# light_sensor_basic.net
KiCad netlist of a schematic drawn in EAGLE
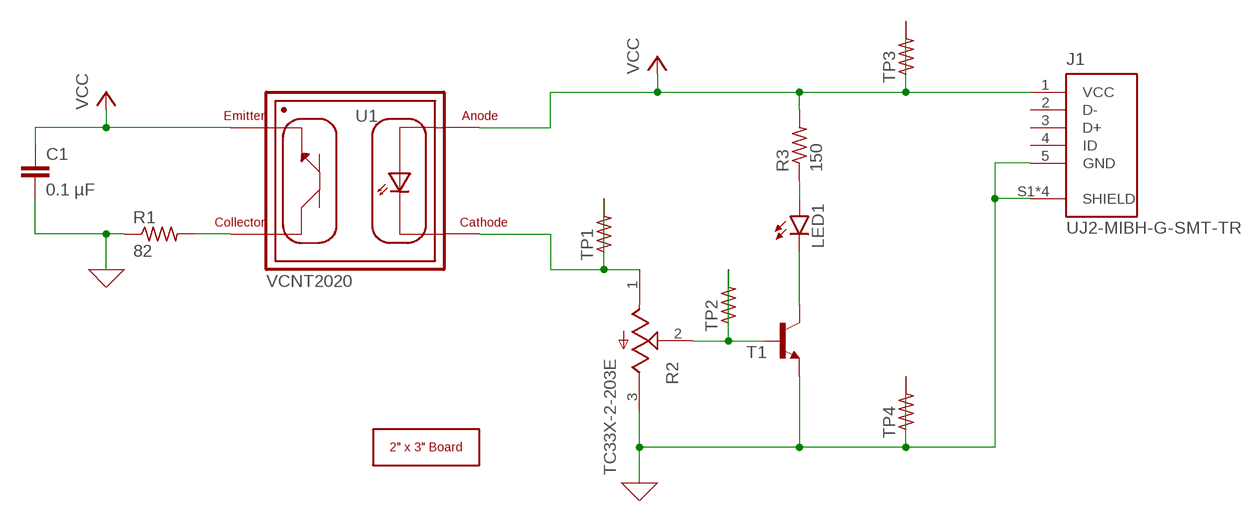
[diagram p0: schematic, sheet 1]

(export (version "E")
  (design (tool "Eeschema 10.0.6"))
  (components
    (comp (ref "C1")
      (value "0.1 µF")
      (footprint "eagle-import:C1206")
      (libsource (lib "eagle-import") (part "C-EUC1206"))
    )
    (comp (ref "J1")
      (value "UJ2-MIBH-G-SMT-TR")
      (footprint "eagle-import:CUI_UJ2-MIBH-G-SMT-TR")
      (fields (field (name "MANUFACTURER") "CUI"))
      (libsource (lib "eagle-import") (part "UJ2-MIBH-G-SMT-TR"))
    )
    (comp (ref "LED1")
      (value "LEDCHIPLED_0805")
      (footprint "eagle-import:CHIPLED_0805")
      (libsource (lib "eagle-import") (part "LEDCHIPLED_0805"))
    )
    (comp (ref "R1")
      (value "82")
      (footprint "eagle-import:R0805")
      (libsource (lib "eagle-import") (part "R-US_R0805"))
    )
    (comp (ref "R2")
      (value "TC33X-2-203E")
      (footprint "eagle-import:TRIM_TC33X-2-203E")
      (fields (field (name "DIGIKEY_PART_NUMBER") "TC33X-2-203ETR-ND") (field (name "MF") "Bourns"))
      (libsource (lib "eagle-import") (part "TC33X-2-203E"))
    )
    (comp (ref "R3")
      (value "150")
      (footprint "eagle-import:R0805")
      (libsource (lib "eagle-import") (part "R-US_R0805"))
    )
    (comp (ref "T1")
      (value "BFS17-NPN-SOT23-BEC")
      (footprint "eagle-import:SOT23-BEC")
      (libsource (lib "eagle-import") (part "-NPN-SOT23-BECBFS17"))
    )
    (comp (ref "TP1")
      (value "R-US_R1206")
      (footprint "eagle-import:R1206")
      (libsource (lib "eagle-import") (part "R-US_R1206"))
    )
    (comp (ref "TP2")
      (value "R-US_R1206")
      (footprint "eagle-import:R1206")
      (libsource (lib "eagle-import") (part "R-US_R1206"))
    )
    (comp (ref "TP3")
      (value "R-US_R1206")
      (footprint "eagle-import:R1206")
      (libsource (lib "eagle-import") (part "R-US_R1206"))
    )
    (comp (ref "TP4")
      (value "R-US_R1206")
      (footprint "eagle-import:R1206")
      (libsource (lib "eagle-import") (part "R-US_R1206"))
    )
    (comp (ref "U$1")
      (value "2X3_BOARD_V2")
      (footprint "eagle-import:2X3_BOARD_V2")
      (libsource (lib "eagle-import") (part "2X3_BOARD_V2"))
    )
    (comp (ref "U1")
      (value "VCNT2020")
      (footprint "eagle-import:XDCR_VCNT2020")
      (fields (field (name "DIGIKEY_PART_NUMBER") "VCNT2020TR-ND") (field (name "MF") "Vishay"))
      (libsource (lib "eagle-import") (part "VCNT2020"))
    )
  )
  (nets
    (net (code "1") (name "GND") (class "Default")
      (node (ref "C1") (pin "2") (pinfunction "2_2") (pintype "passive"))
      (node (ref "J1") (pin "5") (pinfunction "GND_5") (pintype "power_in"))
      (node (ref "J1") (pin "S1") (pinfunction "SHIELD_S1") (pintype "passive"))
      (node (ref "J1") (pin "S2") (pinfunction "SHIELD_S2") (pintype "passive"))
      (node (ref "J1") (pin "S3") (pinfunction "SHIELD_S3") (pintype "passive"))
      (node (ref "J1") (pin "S4") (pinfunction "SHIELD_S4") (pintype "passive"))
      (node (ref "R1") (pin "1") (pinfunction "1_1") (pintype "passive"))
      (node (ref "R2") (pin "3") (pinfunction "CW_3") (pintype "passive"))
      (node (ref "T1") (pin "E") (pinfunction "E_E") (pintype "passive"))
      (node (ref "TP4") (pin "1") (pinfunction "1_1") (pintype "passive"))
      (node (ref "TP4") (pin "2") (pinfunction "2_2") (pintype "passive"))
    )
    (net (code "2") (name "Net-(LED1-PadA)") (class "Default")
      (node (ref "LED1") (pin "A") (pinfunction "A_A") (pintype "passive"))
      (node (ref "R3") (pin "1") (pinfunction "1_1") (pintype "passive"))
    )
    (net (code "3") (name "Net-(LED1-PadC)") (class "Default")
      (node (ref "LED1") (pin "C") (pinfunction "C_C") (pintype "passive"))
      (node (ref "T1") (pin "C") (pinfunction "C_C") (pintype "passive"))
    )
    (net (code "4") (name "Net-(R2-CCW)") (class "Default")
      (node (ref "R2") (pin "1") (pinfunction "CCW_1") (pintype "passive"))
      (node (ref "TP1") (pin "1") (pinfunction "1_1") (pintype "passive"))
      (node (ref "TP1") (pin "2") (pinfunction "2_2") (pintype "passive"))
      (node (ref "U1") (pin "4") (pinfunction "CATHODE_4") (pintype "passive"))
    )
    (net (code "5") (name "Net-(R2-W)") (class "Default")
      (node (ref "R2") (pin "2") (pinfunction "W_2") (pintype "passive"))
      (node (ref "T1") (pin "B") (pinfunction "B_B") (pintype "passive"))
      (node (ref "TP2") (pin "1") (pinfunction "1_1") (pintype "passive"))
      (node (ref "TP2") (pin "2") (pinfunction "2_2") (pintype "passive"))
    )
    (net (code "6") (name "Net-(U1-COLLECTOR)") (class "Default")
      (node (ref "R1") (pin "2") (pinfunction "2_2") (pintype "passive"))
      (node (ref "U1") (pin "2") (pinfunction "COLLECTOR_2") (pintype "passive"))
    )
    (net (code "7") (name "VCC") (class "Default")
      (node (ref "C1") (pin "1") (pinfunction "1_1") (pintype "passive"))
      (node (ref "J1") (pin "1") (pinfunction "VCC_1") (pintype "power_in"))
      (node (ref "R3") (pin "2") (pinfunction "2_2") (pintype "passive"))
      (node (ref "TP3") (pin "1") (pinfunction "1_1") (pintype "passive"))
      (node (ref "TP3") (pin "2") (pinfunction "2_2") (pintype "passive"))
      (node (ref "U1") (pin "1") (pinfunction "EMITTER_1") (pintype "passive"))
      (node (ref "U1") (pin "3") (pinfunction "ANODE_3") (pintype "passive"))
    )
    (net (code "8") (name "unconnected-(J1-D+-Pad3)") (class "Default")
      (node (ref "J1") (pin "3") (pinfunction "D+_3") (pintype "bidirectional"))
    )
    (net (code "9") (name "unconnected-(J1-D--Pad2)") (class "Default")
      (node (ref "J1") (pin "2") (pinfunction "D-_2") (pintype "bidirectional"))
    )
    (net (code "10") (name "unconnected-(J1-ID-Pad4)") (class "Default")
      (node (ref "J1") (pin "4") (pinfunction "ID_4") (pintype "bidirectional"))
    )
  )
)
